# 1750_master_lcd.net
KiCad netlist of a schematic drawn in EAGLE
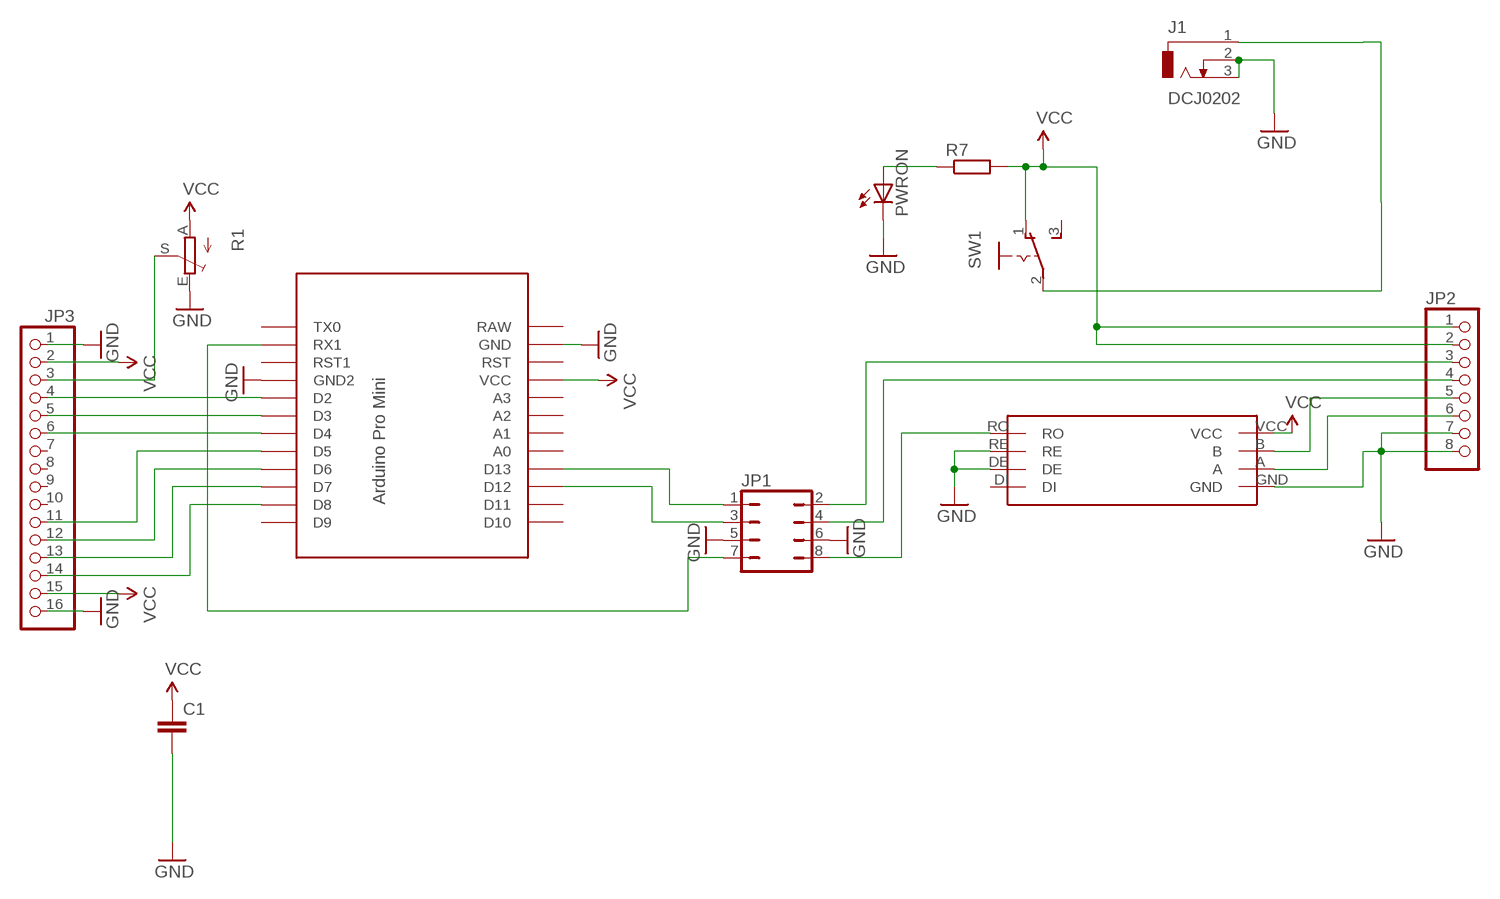
[diagram p0: schematic, sheet 1]

(export (version "E")
  (design (tool "Eeschema 10.0.6"))
  (components
    (comp (ref "C1")
      (value "C-EU025-025X050")
      (footprint "eagle-import:C025-025X050")
      (libsource (lib "eagle-import") (part "C-EU025-025X050"))
    )
    (comp (ref "J1")
      (value "DCJ0202")
      (footprint "eagle-import:DCJ0202")
      (libsource (lib "eagle-import") (part "DCJ0202"))
    )
    (comp (ref "JP1")
      (value "JP4Q")
      (footprint "eagle-import:JP4Q")
      (libsource (lib "eagle-import") (part "JP4Q"))
    )
    (comp (ref "JP2")
      (value "PINHD-1X8")
      (footprint "eagle-import:1X08")
      (libsource (lib "eagle-import") (part "PINHD-1X8"))
    )
    (comp (ref "JP3")
      (value "PINHD-1X16")
      (footprint "eagle-import:1X16")
      (libsource (lib "eagle-import") (part "PINHD-1X16"))
    )
    (comp (ref "PWRON")
      (value "LED5MM")
      (footprint "eagle-import:LED5MM")
      (libsource (lib "eagle-import") (part "LED5MM"))
    )
    (comp (ref "R1")
      (value "TRIM_EU-CA6V")
      (footprint "eagle-import:CA6V")
      (libsource (lib "eagle-import") (part "TRIM_EU-CA6V"))
    )
    (comp (ref "R7")
      (value "R-EU_0207/10")
      (footprint "eagle-import:0207_10")
      (libsource (lib "eagle-import") (part "R-EU_0207/10"))
    )
    (comp (ref "SW1")
      (value "255SB")
      (footprint "eagle-import:255SB")
      (libsource (lib "eagle-import") (part "255SB"))
    )
    (comp (ref "U$2")
      (value "485F")
      (footprint "eagle-import:485F")
      (libsource (lib "eagle-import") (part "485F"))
    )
    (comp (ref "U$3")
      (value "PRO-MINI-F")
      (footprint "eagle-import:PRO-MINI-F")
      (libsource (lib "eagle-import") (part "PRO-MINI-F"))
    )
  )
  (nets
    (net (code "1") (name "GND") (class "Default")
      (node (ref "C1") (pin "2") (pinfunction "2_2") (pintype "passive"))
      (node (ref "J1") (pin "2") (pinfunction "2_2") (pintype "passive"))
      (node (ref "J1") (pin "3") (pinfunction "3_3") (pintype "passive"))
      (node (ref "JP1") (pin "5") (pinfunction "5_5") (pintype "passive"))
      (node (ref "JP1") (pin "6") (pinfunction "6_6") (pintype "passive"))
      (node (ref "JP2") (pin "7") (pinfunction "7_7") (pintype "passive"))
      (node (ref "JP2") (pin "8") (pinfunction "8_8") (pintype "passive"))
      (node (ref "JP3") (pin "1") (pinfunction "1_1") (pintype "passive"))
      (node (ref "JP3") (pin "16") (pinfunction "16_16") (pintype "passive"))
      (node (ref "PWRON") (pin "K") (pinfunction "C_K") (pintype "passive"))
      (node (ref "R1") (pin "E") (pinfunction "E_E") (pintype "passive"))
      (node (ref "U$2") (pin "DE") (pinfunction "DE_DE") (pintype "bidirectional"))
      (node (ref "U$2") (pin "GND") (pinfunction "GND_GND") (pintype "power_in"))
      (node (ref "U$2") (pin "RE") (pinfunction "RE_RE") (pintype "bidirectional"))
      (node (ref "U$3") (pin "GND") (pinfunction "GND_GND") (pintype "bidirectional"))
      (node (ref "U$3") (pin "GND1") (pinfunction "GND2_GND1") (pintype "bidirectional"))
    )
    (net (code "2") (name "Net-(JP1-Pad1)") (class "Default")
      (node (ref "JP1") (pin "1") (pinfunction "1_1") (pintype "passive"))
      (node (ref "U$3") (pin "D13") (pinfunction "D13_D13") (pintype "bidirectional"))
    )
    (net (code "3") (name "Net-(JP1-Pad2)") (class "Default")
      (node (ref "JP1") (pin "2") (pinfunction "2_2") (pintype "passive"))
      (node (ref "JP2") (pin "3") (pinfunction "3_3") (pintype "passive"))
    )
    (net (code "4") (name "Net-(JP1-Pad3)") (class "Default")
      (node (ref "JP1") (pin "3") (pinfunction "3_3") (pintype "passive"))
      (node (ref "U$3") (pin "D12") (pinfunction "D12_D12") (pintype "bidirectional"))
    )
    (net (code "5") (name "Net-(JP1-Pad4)") (class "Default")
      (node (ref "JP1") (pin "4") (pinfunction "4_4") (pintype "passive"))
      (node (ref "JP2") (pin "4") (pinfunction "4_4") (pintype "passive"))
    )
    (net (code "6") (name "Net-(JP1-Pad7)") (class "Default")
      (node (ref "JP1") (pin "7") (pinfunction "7_7") (pintype "passive"))
      (node (ref "U$3") (pin "RX1") (pinfunction "RX1_RX1") (pintype "bidirectional"))
    )
    (net (code "7") (name "Net-(JP1-Pad8)") (class "Default")
      (node (ref "JP1") (pin "8") (pinfunction "8_8") (pintype "passive"))
      (node (ref "U$2") (pin "RO") (pinfunction "RO_RO") (pintype "bidirectional"))
    )
    (net (code "8") (name "Net-(JP2-Pad5)") (class "Default")
      (node (ref "JP2") (pin "5") (pinfunction "5_5") (pintype "passive"))
      (node (ref "U$2") (pin "B") (pinfunction "B_B") (pintype "bidirectional"))
    )
    (net (code "9") (name "Net-(JP2-Pad6)") (class "Default")
      (node (ref "JP2") (pin "6") (pinfunction "6_6") (pintype "passive"))
      (node (ref "U$2") (pin "A") (pinfunction "A_A") (pintype "bidirectional"))
    )
    (net (code "10") (name "Net-(JP3-Pad3)") (class "Default")
      (node (ref "JP3") (pin "3") (pinfunction "3_3") (pintype "passive"))
      (node (ref "R1") (pin "S") (pinfunction "S_S") (pintype "passive"))
    )
    (net (code "11") (name "Net-(JP3-Pad4)") (class "Default")
      (node (ref "JP3") (pin "4") (pinfunction "4_4") (pintype "passive"))
      (node (ref "U$3") (pin "D2") (pinfunction "D2_D2") (pintype "bidirectional"))
    )
    (net (code "12") (name "Net-(JP3-Pad5)") (class "Default")
      (node (ref "JP3") (pin "5") (pinfunction "5_5") (pintype "passive"))
      (node (ref "U$3") (pin "D3") (pinfunction "D3_D3") (pintype "bidirectional"))
    )
    (net (code "13") (name "Net-(JP3-Pad6)") (class "Default")
      (node (ref "JP3") (pin "6") (pinfunction "6_6") (pintype "passive"))
      (node (ref "U$3") (pin "D4") (pinfunction "D4_D4") (pintype "bidirectional"))
    )
    (net (code "14") (name "Net-(JP3-Pad11)") (class "Default")
      (node (ref "JP3") (pin "11") (pinfunction "11_11") (pintype "passive"))
      (node (ref "U$3") (pin "D5") (pinfunction "D5_D5") (pintype "bidirectional"))
    )
    (net (code "15") (name "Net-(JP3-Pad12)") (class "Default")
      (node (ref "JP3") (pin "12") (pinfunction "12_12") (pintype "passive"))
      (node (ref "U$3") (pin "D6") (pinfunction "D6_D6") (pintype "bidirectional"))
    )
    (net (code "16") (name "Net-(JP3-Pad13)") (class "Default")
      (node (ref "JP3") (pin "13") (pinfunction "13_13") (pintype "passive"))
      (node (ref "U$3") (pin "D7") (pinfunction "D7_D7") (pintype "bidirectional"))
    )
    (net (code "17") (name "Net-(JP3-Pad14)") (class "Default")
      (node (ref "JP3") (pin "14") (pinfunction "14_14") (pintype "passive"))
      (node (ref "U$3") (pin "D8") (pinfunction "D8_D8") (pintype "bidirectional"))
    )
    (net (code "18") (name "Net-(PWRON-PadA)") (class "Default")
      (node (ref "PWRON") (pin "A") (pinfunction "A_A") (pintype "passive"))
      (node (ref "R7") (pin "1") (pinfunction "1_1") (pintype "passive"))
    )
    (net (code "19") (name "Net-(SW1-P)") (class "Default")
      (node (ref "J1") (pin "1") (pinfunction "1_1") (pintype "passive"))
      (node (ref "SW1") (pin "2") (pinfunction "P_2") (pintype "passive"))
    )
    (net (code "20") (name "VCC") (class "Default")
      (node (ref "C1") (pin "1") (pinfunction "1_1") (pintype "passive"))
      (node (ref "JP2") (pin "1") (pinfunction "1_1") (pintype "passive"))
      (node (ref "JP2") (pin "2") (pinfunction "2_2") (pintype "passive"))
      (node (ref "JP3") (pin "15") (pinfunction "15_15") (pintype "passive"))
      (node (ref "JP3") (pin "2") (pinfunction "2_2") (pintype "passive"))
      (node (ref "R1") (pin "A") (pinfunction "A_A") (pintype "passive"))
      (node (ref "R7") (pin "2") (pinfunction "2_2") (pintype "passive"))
      (node (ref "SW1") (pin "1") (pinfunction "O_1") (pintype "passive"))
      (node (ref "U$2") (pin "VCC") (pinfunction "VCC_VCC") (pintype "power_in"))
      (node (ref "U$3") (pin "VCC") (pinfunction "VCC_VCC") (pintype "bidirectional"))
    )
    (net (code "21") (name "unconnected-(JP3-Pad7)") (class "Default")
      (node (ref "JP3") (pin "7") (pinfunction "7_7") (pintype "passive"))
    )
    (net (code "22") (name "unconnected-(JP3-Pad8)") (class "Default")
      (node (ref "JP3") (pin "8") (pinfunction "8_8") (pintype "passive"))
    )
    (net (code "23") (name "unconnected-(JP3-Pad9)") (class "Default")
      (node (ref "JP3") (pin "9") (pinfunction "9_9") (pintype "passive"))
    )
    (net (code "24") (name "unconnected-(JP3-Pad10)") (class "Default")
      (node (ref "JP3") (pin "10") (pinfunction "10_10") (pintype "passive"))
    )
    (net (code "25") (name "unconnected-(SW1-S-Pad3)") (class "Default")
      (node (ref "SW1") (pin "3") (pinfunction "S_3") (pintype "passive"))
    )
    (net (code "26") (name "unconnected-(U$2-PadDI)") (class "Default")
      (node (ref "U$2") (pin "DI") (pinfunction "DI_DI") (pintype "bidirectional"))
    )
    (net (code "27") (name "unconnected-(U$3-PadA0)") (class "Default")
      (node (ref "U$3") (pin "A0") (pinfunction "A0_A0") (pintype "bidirectional"))
    )
    (net (code "28") (name "unconnected-(U$3-PadA1)") (class "Default")
      (node (ref "U$3") (pin "A1") (pinfunction "A1_A1") (pintype "bidirectional"))
    )
    (net (code "29") (name "unconnected-(U$3-PadA2)") (class "Default")
      (node (ref "U$3") (pin "A2") (pinfunction "A2_A2") (pintype "bidirectional"))
    )
    (net (code "30") (name "unconnected-(U$3-PadA3)") (class "Default")
      (node (ref "U$3") (pin "A3") (pinfunction "A3_A3") (pintype "bidirectional"))
    )
    (net (code "31") (name "unconnected-(U$3-PadD9)") (class "Default")
      (node (ref "U$3") (pin "D9") (pinfunction "D9_D9") (pintype "bidirectional"))
    )
    (net (code "32") (name "unconnected-(U$3-PadD10)") (class "Default")
      (node (ref "U$3") (pin "D10") (pinfunction "D10_D10") (pintype "bidirectional"))
    )
    (net (code "33") (name "unconnected-(U$3-PadD11)") (class "Default")
      (node (ref "U$3") (pin "D11") (pinfunction "D11_D11") (pintype "bidirectional"))
    )
    (net (code "34") (name "unconnected-(U$3-PadRAW)") (class "Default")
      (node (ref "U$3") (pin "RAW") (pinfunction "RAW_RAW") (pintype "bidirectional"))
    )
    (net (code "35") (name "unconnected-(U$3-PadRST)") (class "Default")
      (node (ref "U$3") (pin "RST") (pinfunction "RST_RST") (pintype "bidirectional"))
    )
    (net (code "36") (name "unconnected-(U$3-PadRST1)") (class "Default")
      (node (ref "U$3") (pin "RST1") (pinfunction "RST1_RST1") (pintype "bidirectional"))
    )
    (net (code "37") (name "unconnected-(U$3-PadTX0)") (class "Default")
      (node (ref "U$3") (pin "TX0") (pinfunction "TX0_TX0") (pintype "bidirectional"))
    )
  )
)
